# Biz-Card-SCH_SH2__A.net
KiCad netlist of a schematic drawn in Altium Designer
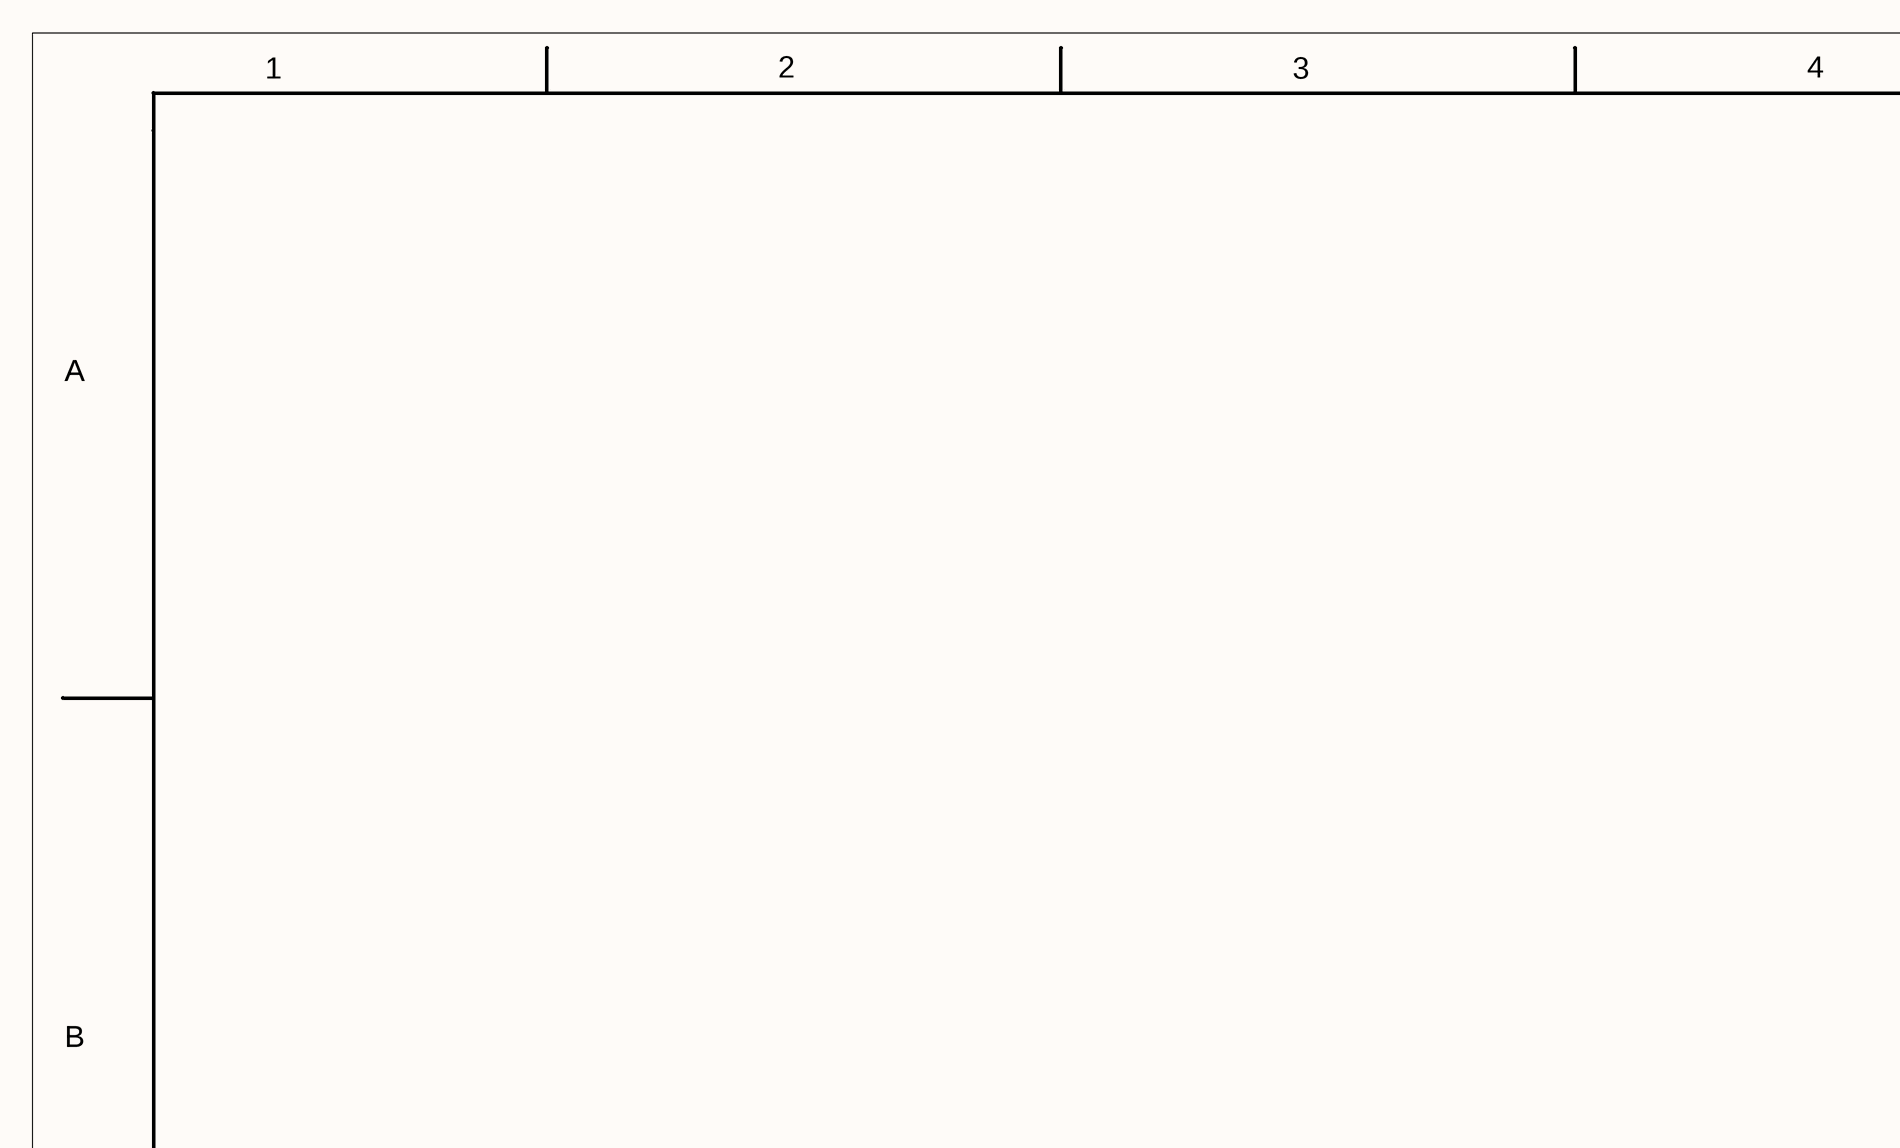
[diagram p0: Biz-Card-SCH_SH2_(A).SchDoc, top left]
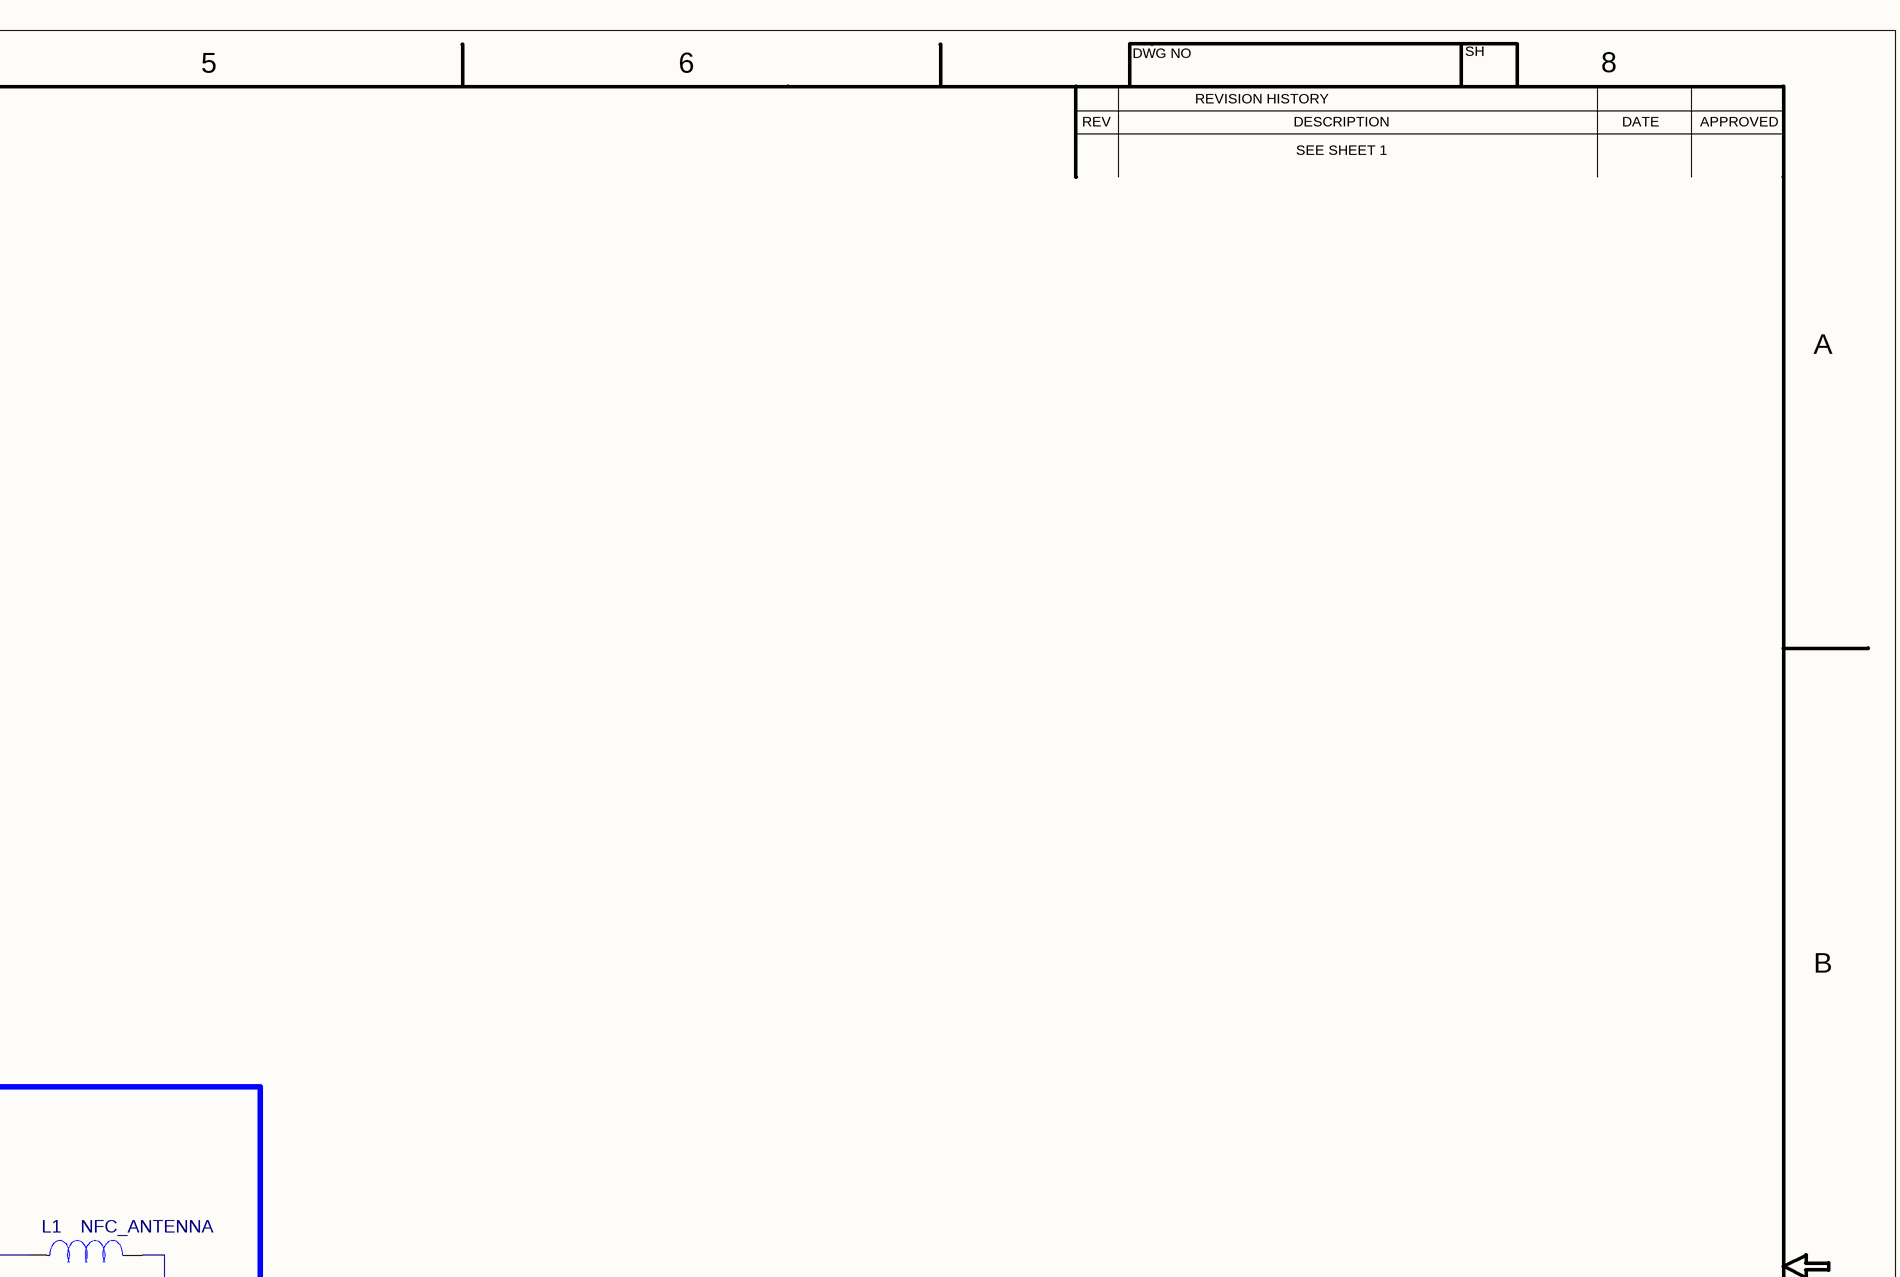
[diagram p1: Biz-Card-SCH_SH2_(A).SchDoc, top right]
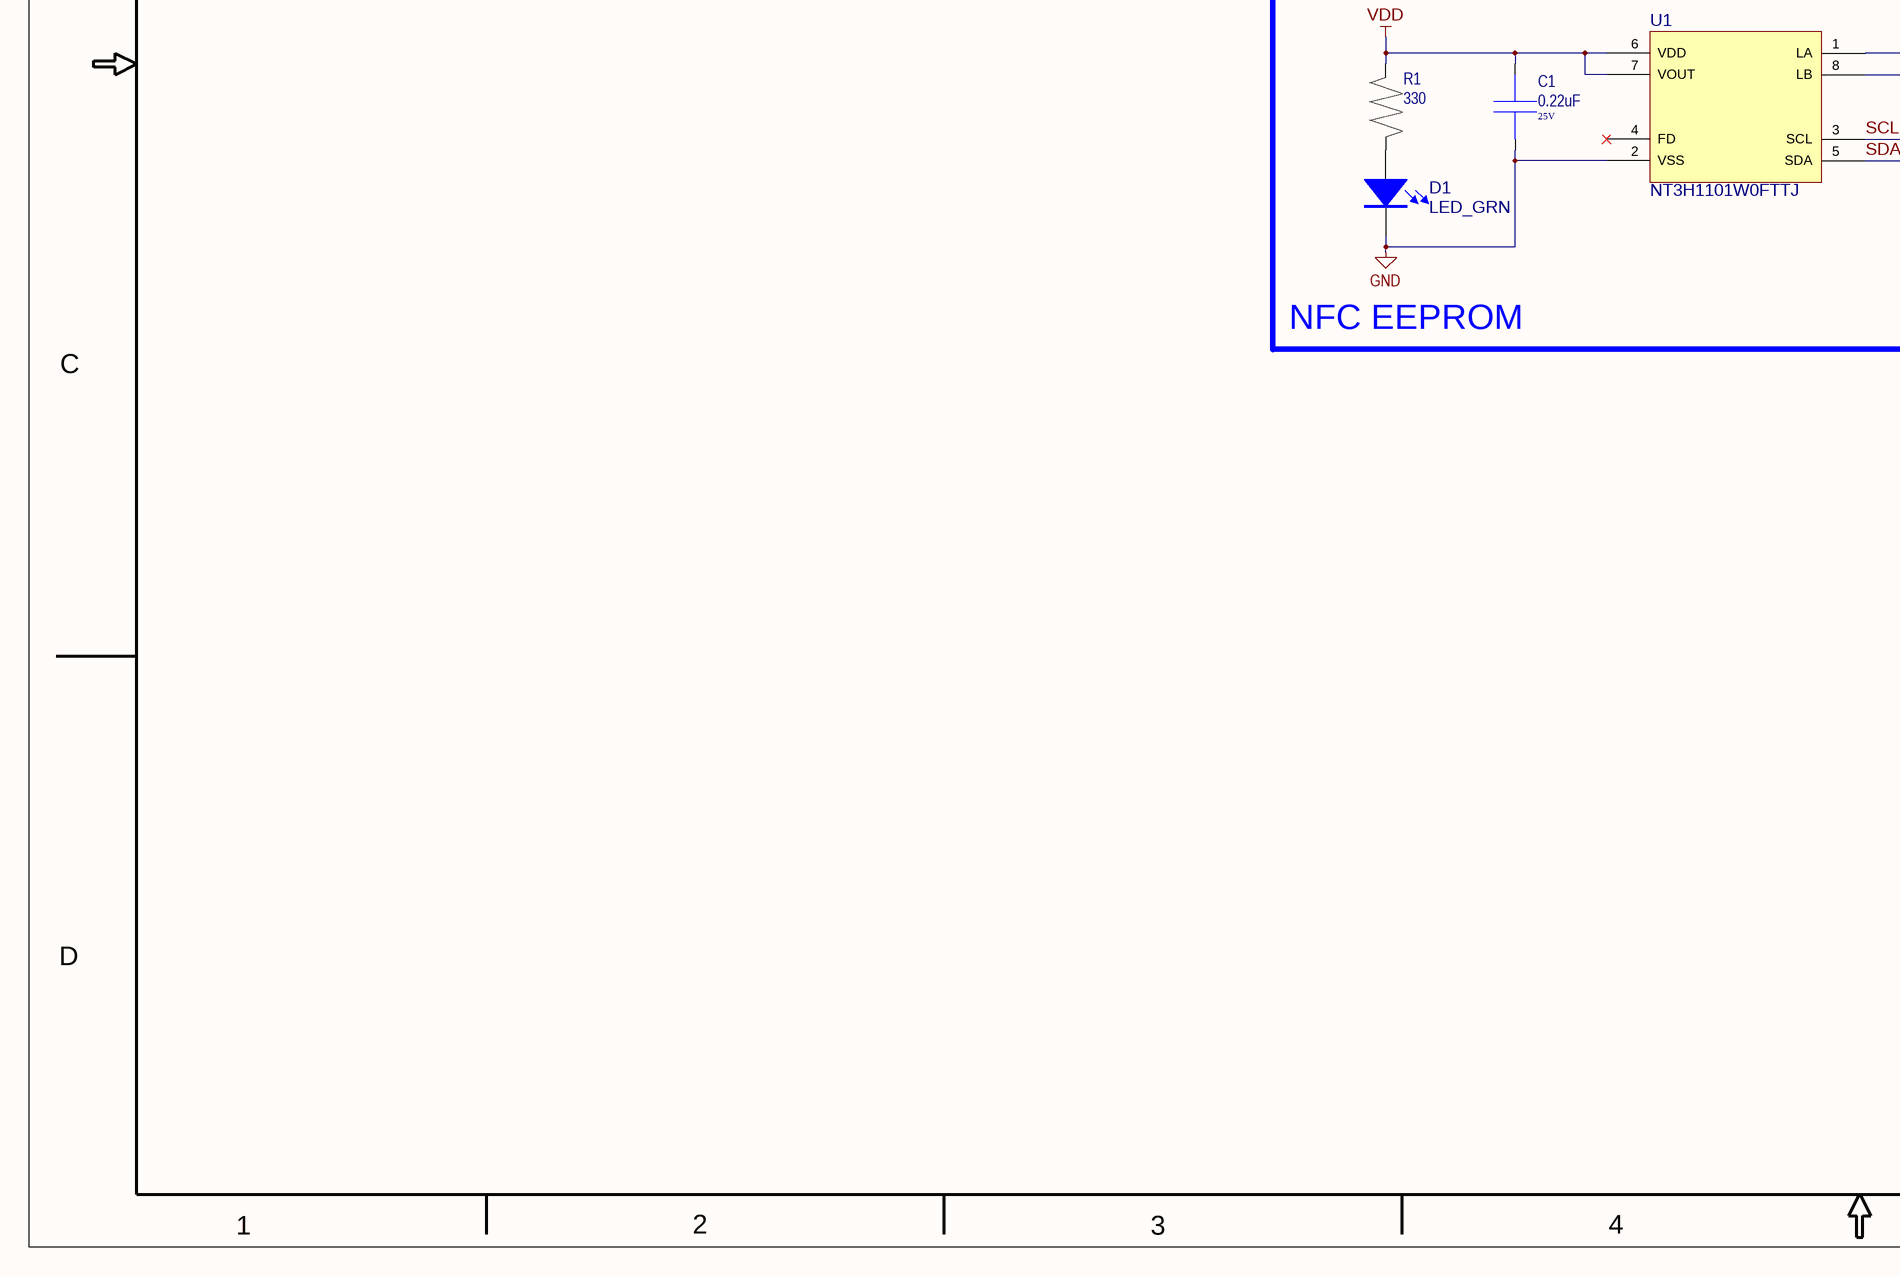
[diagram p2: Biz-Card-SCH_SH2_(A).SchDoc, bottom left]
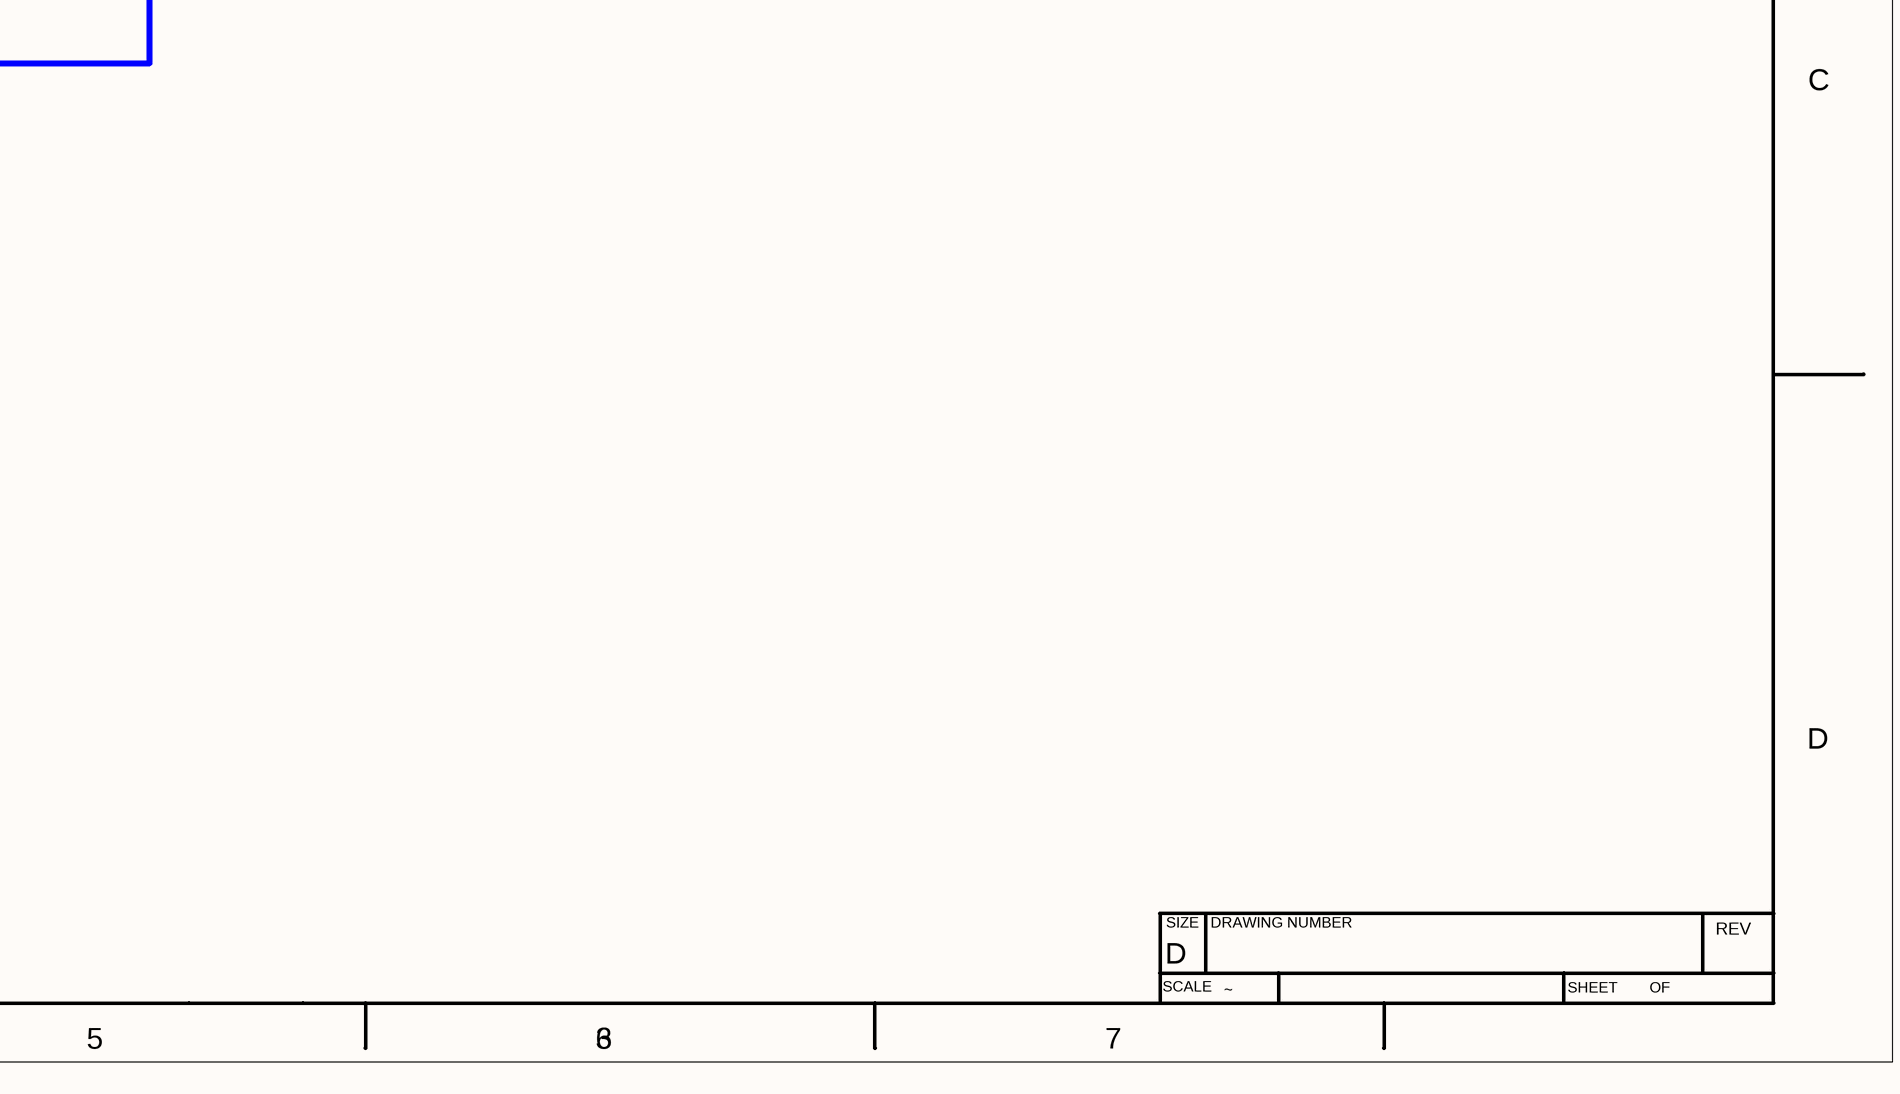
[diagram p3: Biz-Card-SCH_SH2_(A).SchDoc, bottom right]

(export (version "E")
  (design (tool "Eeschema 10.0.6"))
  (components
    (comp (ref "C1")
      (value "0.22uF")
      (footprint "0603")
      (description "CAP CER 0.22UF 25V X7R 0603")
      (fields
        (field (name "PART NUMBER") "CL10B224KA8NNNC")
        (field (name "MANUFACTURER") "Samsung Electro-Mechanics")
        (field (name "VOLTAGE") "25V")
      )
      (libsource (lib "CAPACITORS") (part "CAP"))
    )
    (comp (ref "D1")
      (value "LED_GRN")
      (footprint "1206_LED")
      (description "LED GREEN CLEAR 1206 SMD")
      (fields (field (name "PART NUMBER") "LTST-C150GKT") (field (name "MANUFACTURER") "Lite-On Inc."))
      (libsource (lib "SEMICONDUCTORS") (part "LED"))
    )
    (comp (ref "L1")
      (value "NFC_ANTENNA")
      (footprint "PLANAR_L_50x27mm")
      (description "PLANAR INDUCTOR 27X50 MM")
      (libsource (lib "Peripherals") (part "NFC_ANTENNA"))
    )
    (comp (ref "R1")
      (value "330")
      (footprint "0603")
      (description "RES SMD 330 OHM 1% 1/10W 0603")
      (fields (field (name "PART NUMBER") "CR0603-FX-3300ELF") (field (name "MANUFACTURER") "Bourns Inc."))
      (libsource (lib "RESISTORS") (part "RES"))
    )
    (comp (ref "U1")
      (value "NT3H1101W0FTTJ")
      (footprint "TSSOP-8")
      (description "IC RFID TRANSP 13.56MHZ 8TSSOP")
      (fields (field (name "MANUFACTURER") "NXP USA Inc."))
      (libsource (lib "Peripherals") (part "NT3H1101"))
    )
  )
  (nets
    (net (code "1") (name "/SCL") (class "Default")
      (node (ref "U1") (pin "3") (pinfunction "SCL_3") (pintype "passive"))
    )
    (net (code "2") (name "/SDA") (class "Default")
      (node (ref "U1") (pin "5") (pinfunction "SDA_5") (pintype "power_in"))
    )
    (net (code "3") (name "GND") (class "Default")
      (node (ref "C1") (pin "1") (pinfunction "1_1") (pintype "passive"))
      (node (ref "D1") (pin "2") (pinfunction "K_2") (pintype "passive"))
      (node (ref "U1") (pin "2") (pinfunction "VSS_2") (pintype "passive"))
    )
    (net (code "4") (name "Net-(D1-A)") (class "Default")
      (node (ref "D1") (pin "1") (pinfunction "A_1") (pintype "passive"))
      (node (ref "R1") (pin "1") (pinfunction "1_1") (pintype "passive"))
    )
    (net (code "5") (name "Net-(U1-LA)") (class "Default")
      (node (ref "L1") (pin "2") (pinfunction "2_2") (pintype "passive"))
      (node (ref "U1") (pin "1") (pinfunction "LA_1") (pintype "passive"))
    )
    (net (code "6") (name "Net-(U1-LB)") (class "Default")
      (node (ref "L1") (pin "1") (pinfunction "1_1") (pintype "passive"))
      (node (ref "U1") (pin "8") (pinfunction "LB_8") (pintype "passive"))
    )
    (net (code "7") (name "VDD") (class "Default")
      (node (ref "C1") (pin "2") (pinfunction "2_2") (pintype "passive"))
      (node (ref "R1") (pin "2") (pinfunction "2_2") (pintype "passive"))
      (node (ref "U1") (pin "6") (pinfunction "VDD_6") (pintype "passive"))
      (node (ref "U1") (pin "7") (pinfunction "VOUT_7") (pintype "passive"))
    )
    (net (code "8") (name "unconnected-(U1-FD-Pad4)") (class "Default")
      (node (ref "U1") (pin "4") (pinfunction "FD_4") (pintype "power_in+no_connect"))
    )
  )
)
